# PLL1.net
KiCad netlist of a schematic drawn in Altium Designer
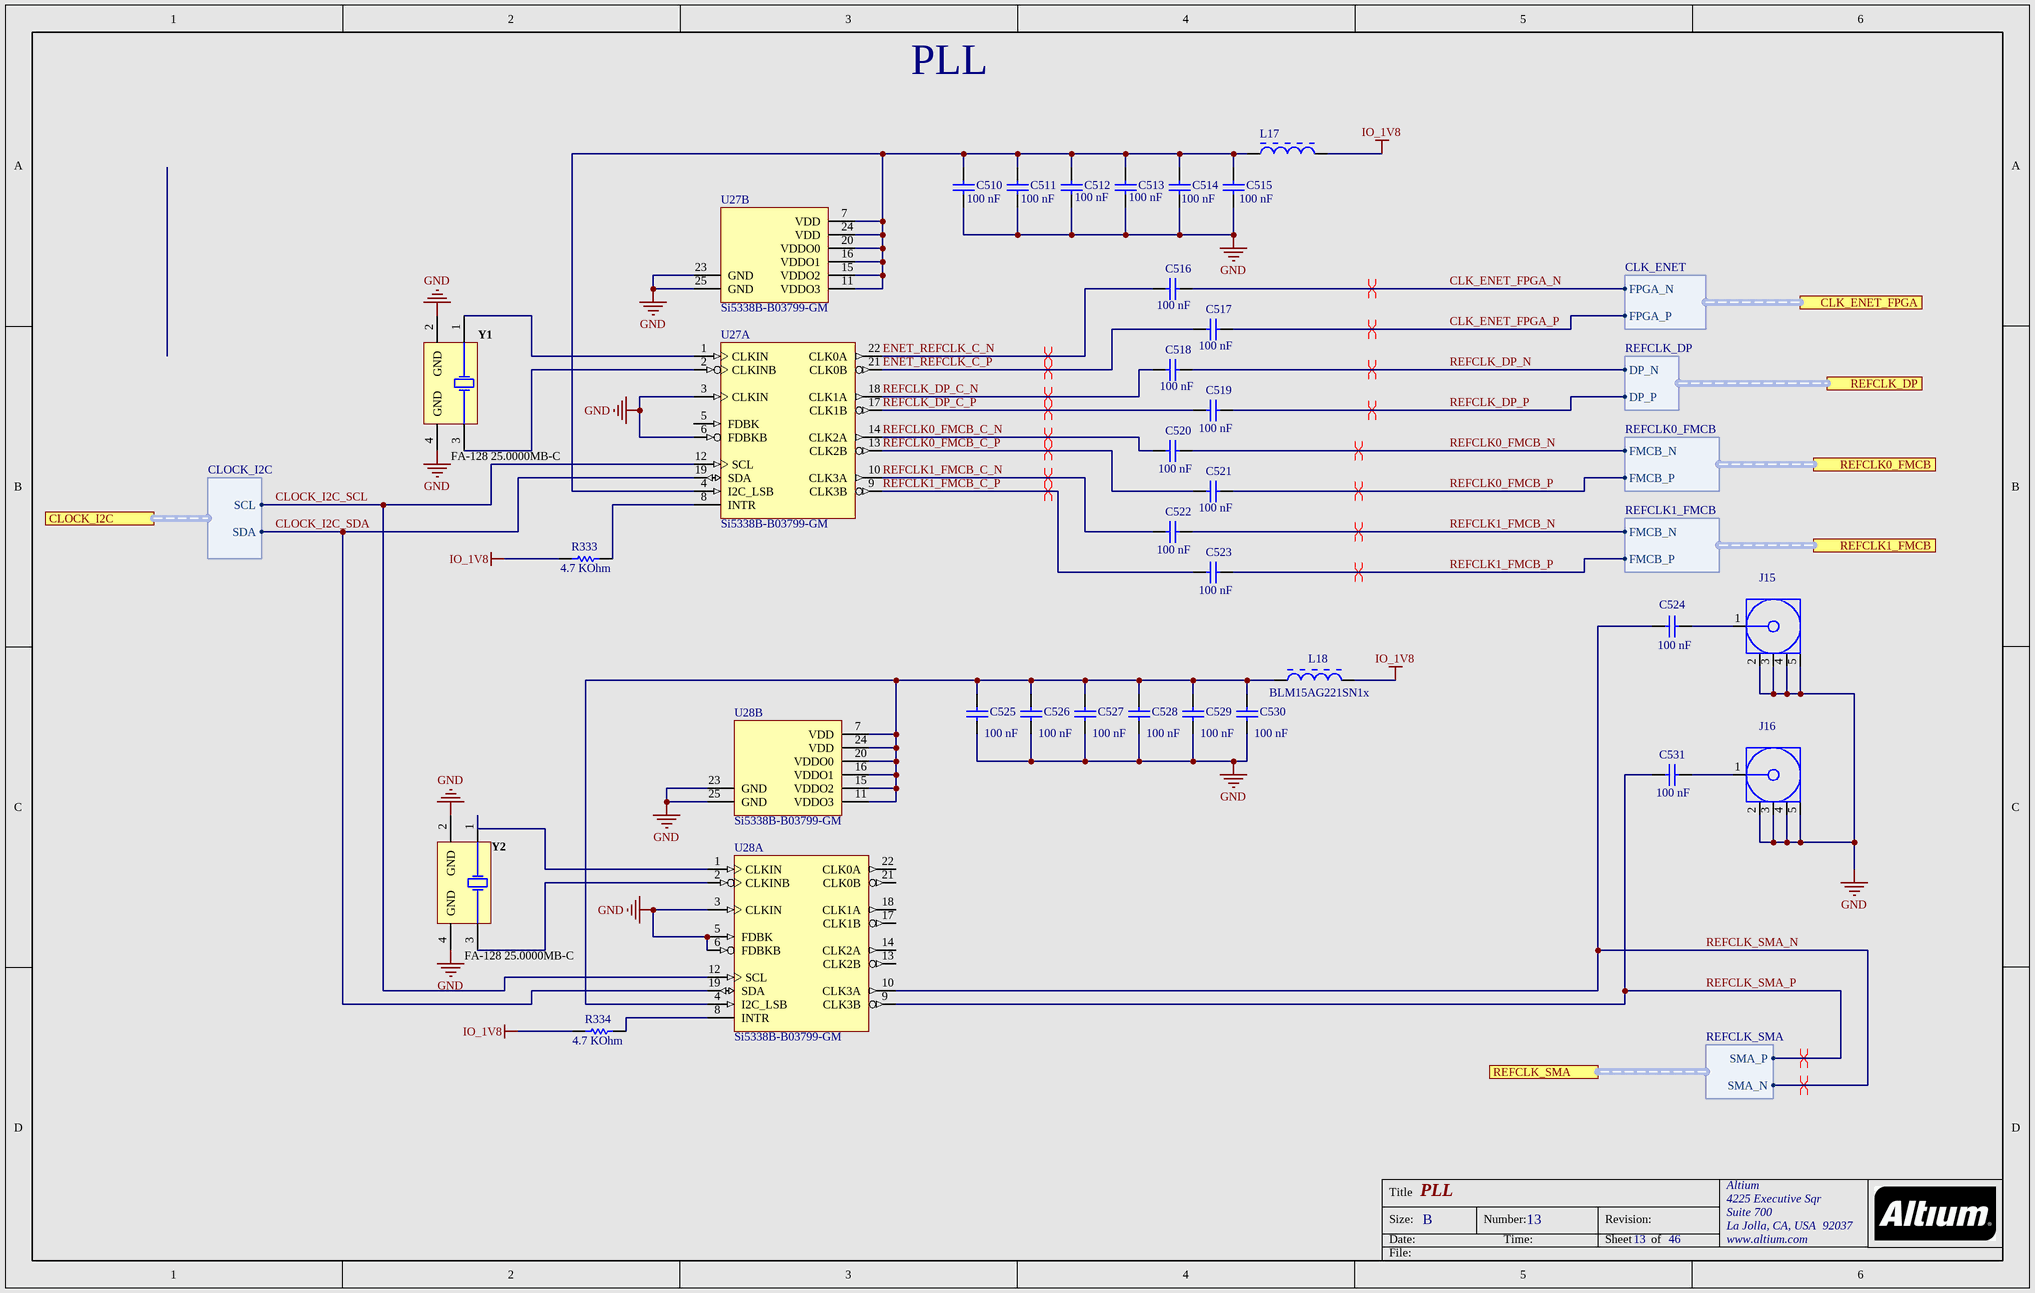
[diagram p0: PLL1.SchDoc]

(export (version "E")
  (design (tool "Eeschema 10.0.6"))
  (components
    (comp (ref "C510")
      (value "C1005X7R1E104M")
      (footprint "CAPC1005X55X10LL05")
      (description "Chip Capacitor, 0.1 uF, +/- 20%, 25 V, -55 to 125 degC, 0402 (1005 Metric), RoHS, Tape and Reel")
      (fields (field (name "TOLERANCE") "20%") (field (name "CAPACITANCE") "100 nF"))
      (libsource (lib "Altium Content Vault") (part "CAP-NP-2"))
    )
    (comp (ref "C511")
      (value "C1005X7R1E104M")
      (footprint "CAPC1005X55X10LL05")
      (description "Chip Capacitor, 0.1 uF, +/- 20%, 25 V, -55 to 125 degC, 0402 (1005 Metric), RoHS, Tape and Reel")
      (fields (field (name "TOLERANCE") "20%") (field (name "CAPACITANCE") "100 nF"))
      (libsource (lib "Altium Content Vault") (part "CAP-NP-2"))
    )
    (comp (ref "C512")
      (value "C1005X7R1E104M")
      (footprint "CAPC1005X55X10LL05")
      (description "Chip Capacitor, 0.1 uF, +/- 20%, 25 V, -55 to 125 degC, 0402 (1005 Metric), RoHS, Tape and Reel")
      (fields (field (name "TOLERANCE") "20%") (field (name "CAPACITANCE") "100 nF"))
      (libsource (lib "Altium Content Vault") (part "CAP-NP-2"))
    )
    (comp (ref "C513")
      (value "C1005X7R1E104M")
      (footprint "CAPC1005X55X10LL05")
      (description "Chip Capacitor, 0.1 uF, +/- 20%, 25 V, -55 to 125 degC, 0402 (1005 Metric), RoHS, Tape and Reel")
      (fields (field (name "TOLERANCE") "20%") (field (name "CAPACITANCE") "100 nF"))
      (libsource (lib "Altium Content Vault") (part "CAP-NP-2"))
    )
    (comp (ref "C514")
      (value "C1005X7R1E104M")
      (footprint "CAPC1005X55X10LL05")
      (description "Chip Capacitor, 0.1 uF, +/- 20%, 25 V, -55 to 125 degC, 0402 (1005 Metric), RoHS, Tape and Reel")
      (fields (field (name "TOLERANCE") "20%") (field (name "CAPACITANCE") "100 nF"))
      (libsource (lib "Altium Content Vault") (part "CAP-NP-2"))
    )
    (comp (ref "C515")
      (value "C1005X7R1E104M")
      (footprint "CAPC1005X55X10LL05")
      (description "Chip Capacitor, 0.1 uF, +/- 20%, 25 V, -55 to 125 degC, 0402 (1005 Metric), RoHS, Tape and Reel")
      (fields (field (name "TOLERANCE") "20%") (field (name "CAPACITANCE") "100 nF"))
      (libsource (lib "Altium Content Vault") (part "CAP-NP-2"))
    )
    (comp (ref "C516")
      (value "C1005X7R1E104M")
      (footprint "CAPC1005X55X10LL05")
      (description "Chip Capacitor, 0.1 uF, +/- 20%, 25 V, -55 to 125 degC, 0402 (1005 Metric), RoHS, Tape and Reel")
      (fields (field (name "TOLERANCE") "20%") (field (name "CAPACITANCE") "100 nF"))
      (libsource (lib "Altium Content Vault") (part "CAP-NP-2"))
    )
    (comp (ref "C517")
      (value "C1005X7R1E104M")
      (footprint "CAPC1005X55X10LL05")
      (description "Chip Capacitor, 0.1 uF, +/- 20%, 25 V, -55 to 125 degC, 0402 (1005 Metric), RoHS, Tape and Reel")
      (fields (field (name "TOLERANCE") "20%") (field (name "CAPACITANCE") "100 nF"))
      (libsource (lib "Altium Content Vault") (part "CAP-NP-2"))
    )
    (comp (ref "C518")
      (value "C1005X7R1E104M")
      (footprint "CAPC1005X55X10LL05")
      (description "Chip Capacitor, 0.1 uF, +/- 20%, 25 V, -55 to 125 degC, 0402 (1005 Metric), RoHS, Tape and Reel")
      (fields (field (name "TOLERANCE") "20%") (field (name "CAPACITANCE") "100 nF"))
      (libsource (lib "Altium Content Vault") (part "CAP-NP-2"))
    )
    (comp (ref "C519")
      (value "C1005X7R1E104M")
      (footprint "CAPC1005X55X10LL05")
      (description "Chip Capacitor, 0.1 uF, +/- 20%, 25 V, -55 to 125 degC, 0402 (1005 Metric), RoHS, Tape and Reel")
      (fields (field (name "TOLERANCE") "20%") (field (name "CAPACITANCE") "100 nF"))
      (libsource (lib "Altium Content Vault") (part "CAP-NP-2"))
    )
    (comp (ref "C520")
      (value "C1005X7R1E104M")
      (footprint "CAPC1005X55X10LL05")
      (description "Chip Capacitor, 0.1 uF, +/- 20%, 25 V, -55 to 125 degC, 0402 (1005 Metric), RoHS, Tape and Reel")
      (fields (field (name "TOLERANCE") "20%") (field (name "CAPACITANCE") "100 nF"))
      (libsource (lib "Altium Content Vault") (part "CAP-NP-2"))
    )
    (comp (ref "C521")
      (value "C1005X7R1E104M")
      (footprint "CAPC1005X55X10LL05")
      (description "Chip Capacitor, 0.1 uF, +/- 20%, 25 V, -55 to 125 degC, 0402 (1005 Metric), RoHS, Tape and Reel")
      (fields (field (name "TOLERANCE") "20%") (field (name "CAPACITANCE") "100 nF"))
      (libsource (lib "Altium Content Vault") (part "CAP-NP-2"))
    )
    (comp (ref "C522")
      (value "C1005X7R1E104M")
      (footprint "CAPC1005X55X10LL05")
      (description "Chip Capacitor, 0.1 uF, +/- 20%, 25 V, -55 to 125 degC, 0402 (1005 Metric), RoHS, Tape and Reel")
      (fields (field (name "TOLERANCE") "20%") (field (name "CAPACITANCE") "100 nF"))
      (libsource (lib "Altium Content Vault") (part "CAP-NP-2"))
    )
    (comp (ref "C523")
      (value "C1005X7R1E104M")
      (footprint "CAPC1005X55X10LL05")
      (description "Chip Capacitor, 0.1 uF, +/- 20%, 25 V, -55 to 125 degC, 0402 (1005 Metric), RoHS, Tape and Reel")
      (fields (field (name "TOLERANCE") "20%") (field (name "CAPACITANCE") "100 nF"))
      (libsource (lib "Altium Content Vault") (part "CAP-NP-2"))
    )
    (comp (ref "C524")
      (value "C1005X7R1E104M")
      (footprint "CAPC1005X55X10LL05")
      (description "Chip Capacitor, 0.1 uF, +/- 20%, 25 V, -55 to 125 degC, 0402 (1005 Metric), RoHS, Tape and Reel")
      (fields (field (name "TOLERANCE") "20%") (field (name "CAPACITANCE") "100 nF"))
      (libsource (lib "Altium Content Vault") (part "CAP-NP-2"))
    )
    (comp (ref "C525")
      (value "C1005X7R1E104M")
      (footprint "CAPC1005X55X10LL05")
      (description "Chip Capacitor, 0.1 uF, +/- 20%, 25 V, -55 to 125 degC, 0402 (1005 Metric), RoHS, Tape and Reel")
      (fields (field (name "TOLERANCE") "20%") (field (name "CAPACITANCE") "100 nF"))
      (libsource (lib "Altium Content Vault") (part "CAP-NP-2"))
    )
    (comp (ref "C526")
      (value "C1005X7R1E104M")
      (footprint "CAPC1005X55X10LL05")
      (description "Chip Capacitor, 0.1 uF, +/- 20%, 25 V, -55 to 125 degC, 0402 (1005 Metric), RoHS, Tape and Reel")
      (fields (field (name "TOLERANCE") "20%") (field (name "CAPACITANCE") "100 nF"))
      (libsource (lib "Altium Content Vault") (part "CAP-NP-2"))
    )
    (comp (ref "C527")
      (value "C1005X7R1E104M")
      (footprint "CAPC1005X55X10LL05")
      (description "Chip Capacitor, 0.1 uF, +/- 20%, 25 V, -55 to 125 degC, 0402 (1005 Metric), RoHS, Tape and Reel")
      (fields (field (name "TOLERANCE") "20%") (field (name "CAPACITANCE") "100 nF"))
      (libsource (lib "Altium Content Vault") (part "CAP-NP-2"))
    )
    (comp (ref "C528")
      (value "C1005X7R1E104M")
      (footprint "CAPC1005X55X10LL05")
      (description "Chip Capacitor, 0.1 uF, +/- 20%, 25 V, -55 to 125 degC, 0402 (1005 Metric), RoHS, Tape and Reel")
      (fields (field (name "TOLERANCE") "20%") (field (name "CAPACITANCE") "100 nF"))
      (libsource (lib "Altium Content Vault") (part "CAP-NP-2"))
    )
    (comp (ref "C529")
      (value "C1005X7R1E104M")
      (footprint "CAPC1005X55X10LL05")
      (description "Chip Capacitor, 0.1 uF, +/- 20%, 25 V, -55 to 125 degC, 0402 (1005 Metric), RoHS, Tape and Reel")
      (fields (field (name "TOLERANCE") "20%") (field (name "CAPACITANCE") "100 nF"))
      (libsource (lib "Altium Content Vault") (part "CAP-NP-2"))
    )
    (comp (ref "C530")
      (value "C1005X7R1E104M")
      (footprint "CAPC1005X55X10LL05")
      (description "Chip Capacitor, 0.1 uF, +/- 20%, 25 V, -55 to 125 degC, 0402 (1005 Metric), RoHS, Tape and Reel")
      (fields (field (name "TOLERANCE") "20%") (field (name "CAPACITANCE") "100 nF"))
      (libsource (lib "Altium Content Vault") (part "CAP-NP-2"))
    )
    (comp (ref "C531")
      (value "C1005X7R1E104M")
      (footprint "CAPC1005X55X10LL05")
      (description "Chip Capacitor, 0.1 uF, +/- 20%, 25 V, -55 to 125 degC, 0402 (1005 Metric), RoHS, Tape and Reel")
      (fields (field (name "TOLERANCE") "20%") (field (name "CAPACITANCE") "100 nF"))
      (libsource (lib "Altium Content Vault") (part "CAP-NP-2"))
    )
    (comp (ref "J15")
      (value "LTI-SASF54GT")
      (footprint "LHT-LTI-SASF54GT_V")
      (description "SMA Connector, Pitch 2.54 mm, 1 Position, Height 9.5 mm, Tail Length 4 mm, RoHS")
      (fields (field (name "MANUFACTURER") "Lighthorse Technologies Inc."))
      (libsource (lib "Altium Content Vault") (part "CMP-1713-00001-1"))
    )
    (comp (ref "J16")
      (value "LTI-SASF54GT")
      (footprint "LHT-LTI-SASF54GT_V")
      (description "SMA Connector, Pitch 2.54 mm, 1 Position, Height 9.5 mm, Tail Length 4 mm, RoHS")
      (fields (field (name "MANUFACTURER") "Lighthorse Technologies Inc."))
      (libsource (lib "Altium Content Vault") (part "CMP-1713-00001-1"))
    )
    (comp (ref "L17")
      (value "BLM15AG221SN1J")
      (footprint "MURA-BLM15-CHIP-2_V")
      (fields (field (name "MANUFACTURER") "Murata"))
      (libsource (lib "Altium Content Vault") (part "CMP-0686-00186-2"))
    )
    (comp (ref "L18")
      (value "BLM15AG221SN1x")
      (footprint "MURA-BLM15AG221SN1x_V")
      (description "Chip Bead, 220 Ohm, +/- 25 %, 100 MHz, 300 mA, -55 to 125 degC, 0402 (1005 Metric), RoHS")
      (fields (field (name "TOLERANCE") "25%"))
      (libsource (lib "Altium Content Vault") (part "BEAD-2"))
    )
    (comp (ref "R333")
      (value "ERJ-2RKF4701X")
      (footprint "RESC1005X40X25LL05T05")
      (description "Chip Resistor, 4.7 KOhm, +/- 1%, 0.1 W, -55 to 155 degC, 0402 (1005 Metric), RoHS, Tape and Reel")
      (fields (field (name "TOLERANCE") "1%") (field (name "RESISTANCE") "4.7 KOhm"))
      (libsource (lib "Altium Content Vault") (part "RES-2"))
    )
    (comp (ref "R334")
      (value "ERJ-2RKF4701X")
      (footprint "RESC1005X40X25LL05T05")
      (description "Chip Resistor, 4.7 KOhm, +/- 1%, 0.1 W, -55 to 155 degC, 0402 (1005 Metric), RoHS, Tape and Reel")
      (fields (field (name "TOLERANCE") "1%") (field (name "RESISTANCE") "4.7 KOhm"))
      (libsource (lib "Altium Content Vault") (part "RES-2"))
    )
    (comp (ref "U27")
      (value "Si5338B-B03799-GM")
      (footprint "SLAB-QFN-24-2550x2550TP_V")
      (fields (field (name "MANUFACTURER") "Silicon Labs"))
      (libsource (lib "") (part "CMP-1706-00002-1_1"))
    )
    (comp (ref "U28")
      (value "Si5338B-B03799-GM")
      (footprint "SLAB-QFN-24-2550x2550TP_V")
      (fields (field (name "MANUFACTURER") "Silicon Labs"))
      (libsource (lib "Altium Content Vault") (part "CMP-1706-00002-1"))
    )
    (comp (ref "Y1")
      (value "FA-128 25.0000MB-C")
      (footprint "EPSON-FA-128_V")
      (description "Range Crystal Unit, 25 MHz, -40 to 85 degC, 4-Pin SMD, RoHS, Tape and Reel")
      (libsource (lib "Altium Content Vault") (part "XTAL-1-3-4"))
    )
    (comp (ref "Y2")
      (value "FA-128 25.0000MB-C")
      (footprint "EPSON-FA-128_V")
      (description "Range Crystal Unit, 25 MHz, -40 to 85 degC, 4-Pin SMD, RoHS, Tape and Reel")
      (libsource (lib "Altium Content Vault") (part "XTAL-1-3-4"))
    )
  )
  (nets
    (net (code "7") (name "/CLK_ENET_FPGA_N") (class "Default")
      (node (ref "C516") (pin "2") (pinfunction "2_2") (pintype "passive"))
    )
    (net (code "8") (name "/CLK_ENET_FPGA_P") (class "Default")
      (node (ref "C517") (pin "2") (pinfunction "2_2") (pintype "passive"))
    )
    (net (code "9") (name "/CLOCK_I2C_SCL") (class "Default")
      (node (ref "U27") (pin "12") (pinfunction "SCL_12") (pintype "input"))
      (node (ref "U28") (pin "12") (pinfunction "SCL_12") (pintype "input"))
    )
    (net (code "10") (name "/CLOCK_I2C_SDA") (class "Default")
      (node (ref "U27") (pin "19") (pinfunction "SDA_19") (pintype "bidirectional"))
      (node (ref "U28") (pin "19") (pinfunction "SDA_19") (pintype "bidirectional"))
    )
    (net (code "11") (name "/ENET_REFCLK_C_N") (class "Default")
      (node (ref "C516") (pin "1") (pinfunction "1_1") (pintype "passive"))
      (node (ref "U27") (pin "22") (pinfunction "CLK0A_22") (pintype "output"))
    )
    (net (code "12") (name "/ENET_REFCLK_C_P") (class "Default")
      (node (ref "C517") (pin "1") (pinfunction "1_1") (pintype "passive"))
      (node (ref "U27") (pin "21") (pinfunction "CLK0B_21") (pintype "output"))
    )
    (net (code "13") (name "/REFCLK0_FMCB_C_N") (class "Default")
      (node (ref "C520") (pin "1") (pinfunction "1_1") (pintype "passive"))
      (node (ref "U27") (pin "14") (pinfunction "CLK2A_14") (pintype "output"))
    )
    (net (code "14") (name "/REFCLK0_FMCB_C_P") (class "Default")
      (node (ref "C521") (pin "1") (pinfunction "1_1") (pintype "passive"))
      (node (ref "U27") (pin "13") (pinfunction "CLK2B_13") (pintype "output"))
    )
    (net (code "15") (name "/REFCLK0_FMCB_N") (class "Default")
      (node (ref "C520") (pin "2") (pinfunction "2_2") (pintype "passive"))
    )
    (net (code "16") (name "/REFCLK0_FMCB_P") (class "Default")
      (node (ref "C521") (pin "2") (pinfunction "2_2") (pintype "passive"))
    )
    (net (code "17") (name "/REFCLK1_FMCB_C_N") (class "Default")
      (node (ref "C522") (pin "1") (pinfunction "1_1") (pintype "passive"))
      (node (ref "U27") (pin "10") (pinfunction "CLK3A_10") (pintype "output"))
    )
    (net (code "18") (name "/REFCLK1_FMCB_C_P") (class "Default")
      (node (ref "C523") (pin "1") (pinfunction "1_1") (pintype "passive"))
      (node (ref "U27") (pin "9") (pinfunction "CLK3B_9") (pintype "output"))
    )
    (net (code "19") (name "/REFCLK1_FMCB_N") (class "Default")
      (node (ref "C522") (pin "2") (pinfunction "2_2") (pintype "passive"))
    )
    (net (code "20") (name "/REFCLK1_FMCB_P") (class "Default")
      (node (ref "C523") (pin "2") (pinfunction "2_2") (pintype "passive"))
    )
    (net (code "21") (name "/REFCLK_DP_C_N") (class "Default")
      (node (ref "C518") (pin "1") (pinfunction "1_1") (pintype "passive"))
      (node (ref "U27") (pin "18") (pinfunction "CLK1A_18") (pintype "output"))
    )
    (net (code "22") (name "/REFCLK_DP_C_P") (class "Default")
      (node (ref "C519") (pin "1") (pinfunction "1_1") (pintype "passive"))
      (node (ref "U27") (pin "17") (pinfunction "CLK1B_17") (pintype "output"))
    )
    (net (code "23") (name "/REFCLK_DP_N") (class "Default")
      (node (ref "C518") (pin "2") (pinfunction "2_2") (pintype "passive"))
    )
    (net (code "24") (name "/REFCLK_DP_P") (class "Default")
      (node (ref "C519") (pin "2") (pinfunction "2_2") (pintype "passive"))
    )
    (net (code "25") (name "/REFCLK_SMA_N") (class "Default")
      (node (ref "C524") (pin "1") (pinfunction "1_1") (pintype "passive"))
      (node (ref "U28") (pin "10") (pinfunction "CLK3A_10") (pintype "output"))
    )
    (net (code "26") (name "/REFCLK_SMA_P") (class "Default")
      (node (ref "C531") (pin "1") (pinfunction "1_1") (pintype "passive"))
      (node (ref "U28") (pin "9") (pinfunction "CLK3B_9") (pintype "output"))
    )
    (net (code "33") (name "GND") (class "Default")
      (node (ref "C510") (pin "2") (pinfunction "2_2") (pintype "passive"))
      (node (ref "C511") (pin "2") (pinfunction "2_2") (pintype "passive"))
      (node (ref "C512") (pin "2") (pinfunction "2_2") (pintype "passive"))
      (node (ref "C513") (pin "2") (pinfunction "2_2") (pintype "passive"))
      (node (ref "C514") (pin "2") (pinfunction "2_2") (pintype "passive"))
      (node (ref "C515") (pin "2") (pinfunction "2_2") (pintype "passive"))
      (node (ref "C525") (pin "2") (pinfunction "2_2") (pintype "passive"))
      (node (ref "C526") (pin "2") (pinfunction "2_2") (pintype "passive"))
      (node (ref "C527") (pin "2") (pinfunction "2_2") (pintype "passive"))
      (node (ref "C528") (pin "2") (pinfunction "2_2") (pintype "passive"))
      (node (ref "C529") (pin "2") (pinfunction "2_2") (pintype "passive"))
      (node (ref "C530") (pin "2") (pinfunction "2_2") (pintype "passive"))
      (node (ref "J15") (pin "2") (pinfunction "2_2") (pintype "passive"))
      (node (ref "J15") (pin "3") (pinfunction "3_3") (pintype "passive"))
      (node (ref "J15") (pin "4") (pinfunction "4_4") (pintype "passive"))
      (node (ref "J15") (pin "5") (pinfunction "5_5") (pintype "passive"))
      (node (ref "J16") (pin "2") (pinfunction "2_2") (pintype "passive"))
      (node (ref "J16") (pin "3") (pinfunction "3_3") (pintype "passive"))
      (node (ref "J16") (pin "4") (pinfunction "4_4") (pintype "passive"))
      (node (ref "J16") (pin "5") (pinfunction "5_5") (pintype "passive"))
      (node (ref "U27") (pin "23") (pinfunction "GND_23") (pintype "power_in"))
      (node (ref "U27") (pin "25") (pinfunction "GND_25") (pintype "power_in"))
      (node (ref "U27") (pin "3") (pinfunction "CLKIN_3") (pintype "input"))
      (node (ref "U27") (pin "6") (pinfunction "FDBKB_6") (pintype "input"))
      (node (ref "U28") (pin "23") (pinfunction "GND_23") (pintype "power_in"))
      (node (ref "U28") (pin "25") (pinfunction "GND_25") (pintype "power_in"))
      (node (ref "U28") (pin "3") (pinfunction "CLKIN_3") (pintype "input"))
      (node (ref "U28") (pin "5") (pinfunction "FDBK_5") (pintype "input"))
      (node (ref "U28") (pin "6") (pinfunction "FDBKB_6") (pintype "input"))
      (node (ref "Y1") (pin "2") (pinfunction "GND_2") (pintype "power_in"))
      (node (ref "Y1") (pin "4") (pinfunction "GND_4") (pintype "power_in"))
      (node (ref "Y2") (pin "2") (pinfunction "GND_2") (pintype "power_in"))
      (node (ref "Y2") (pin "4") (pinfunction "GND_4") (pintype "power_in"))
    )
    (net (code "34") (name "IO_1V8") (class "Default")
      (node (ref "L17") (pin "2") (pinfunction "2_2") (pintype "passive"))
      (node (ref "L18") (pin "2") (pinfunction "2_2") (pintype "passive"))
      (node (ref "R333") (pin "1") (pinfunction "1_1") (pintype "passive"))
      (node (ref "R334") (pin "1") (pinfunction "1_1") (pintype "passive"))
    )
    (net (code "35") (name "Net-(C524-Pad2)") (class "Default")
      (node (ref "C524") (pin "2") (pinfunction "2_2") (pintype "passive"))
      (node (ref "J15") (pin "1") (pinfunction "1_1") (pintype "passive"))
    )
    (net (code "36") (name "Net-(C531-Pad2)") (class "Default")
      (node (ref "C531") (pin "2") (pinfunction "2_2") (pintype "passive"))
      (node (ref "J16") (pin "1") (pinfunction "1_1") (pintype "passive"))
    )
    (net (code "37") (name "Net-(U27A-CLKINB)") (class "Default")
      (node (ref "U27") (pin "2") (pinfunction "CLKINB_2") (pintype "input"))
      (node (ref "Y1") (pin "3") (pinfunction "X2_3") (pintype "passive"))
    )
    (net (code "38") (name "Net-(U27A-I2C_LSB)") (class "Default")
      (node (ref "C510") (pin "1") (pinfunction "1_1") (pintype "passive"))
      (node (ref "C511") (pin "1") (pinfunction "1_1") (pintype "passive"))
      (node (ref "C512") (pin "1") (pinfunction "1_1") (pintype "passive"))
      (node (ref "C513") (pin "1") (pinfunction "1_1") (pintype "passive"))
      (node (ref "C514") (pin "1") (pinfunction "1_1") (pintype "passive"))
      (node (ref "C515") (pin "1") (pinfunction "1_1") (pintype "passive"))
      (node (ref "L17") (pin "1") (pinfunction "1_1") (pintype "passive"))
      (node (ref "U27") (pin "11") (pinfunction "VDDO3_11") (pintype "power_in"))
      (node (ref "U27") (pin "15") (pinfunction "VDDO2_15") (pintype "power_in"))
      (node (ref "U27") (pin "16") (pinfunction "VDDO1_16") (pintype "power_in"))
      (node (ref "U27") (pin "20") (pinfunction "VDDO0_20") (pintype "power_in"))
      (node (ref "U27") (pin "24") (pinfunction "VDD_24") (pintype "power_in"))
      (node (ref "U27") (pin "4") (pinfunction "I2C_LSB_4") (pintype "input"))
      (node (ref "U27") (pin "7") (pinfunction "VDD_7") (pintype "power_in"))
    )
    (net (code "39") (name "Net-(U27A-INTR)") (class "Default")
      (node (ref "R333") (pin "2") (pinfunction "2_2") (pintype "passive"))
      (node (ref "U27") (pin "8") (pinfunction "INTR_8") (pintype "open_collector"))
    )
    (net (code "40") (name "Net-(U28A-CLKINB)") (class "Default")
      (node (ref "U28") (pin "2") (pinfunction "CLKINB_2") (pintype "input"))
      (node (ref "Y2") (pin "3") (pinfunction "X2_3") (pintype "passive"))
    )
    (net (code "41") (name "Net-(U28A-I2C_LSB)") (class "Default")
      (node (ref "C525") (pin "1") (pinfunction "1_1") (pintype "passive"))
      (node (ref "C526") (pin "1") (pinfunction "1_1") (pintype "passive"))
      (node (ref "C527") (pin "1") (pinfunction "1_1") (pintype "passive"))
      (node (ref "C528") (pin "1") (pinfunction "1_1") (pintype "passive"))
      (node (ref "C529") (pin "1") (pinfunction "1_1") (pintype "passive"))
      (node (ref "C530") (pin "1") (pinfunction "1_1") (pintype "passive"))
      (node (ref "L18") (pin "1") (pinfunction "1_1") (pintype "passive"))
      (node (ref "U28") (pin "11") (pinfunction "VDDO3_11") (pintype "power_in"))
      (node (ref "U28") (pin "15") (pinfunction "VDDO2_15") (pintype "power_in"))
      (node (ref "U28") (pin "16") (pinfunction "VDDO1_16") (pintype "power_in"))
      (node (ref "U28") (pin "20") (pinfunction "VDDO0_20") (pintype "power_in"))
      (node (ref "U28") (pin "24") (pinfunction "VDD_24") (pintype "power_in"))
      (node (ref "U28") (pin "4") (pinfunction "I2C_LSB_4") (pintype "input"))
      (node (ref "U28") (pin "7") (pinfunction "VDD_7") (pintype "power_in"))
    )
    (net (code "42") (name "Net-(U28A-INTR)") (class "Default")
      (node (ref "R334") (pin "2") (pinfunction "2_2") (pintype "passive"))
      (node (ref "U28") (pin "8") (pinfunction "INTR_8") (pintype "open_collector"))
    )
    (net (code "43") (name "Net-(Y1-X1)") (class "Default")
      (node (ref "U27") (pin "1") (pinfunction "CLKIN_1") (pintype "input"))
      (node (ref "Y1") (pin "1") (pinfunction "X1_1") (pintype "passive"))
    )
    (net (code "44") (name "Net-(Y2-X1)") (class "Default")
      (node (ref "U28") (pin "1") (pinfunction "CLKIN_1") (pintype "input"))
      (node (ref "Y2") (pin "1") (pinfunction "X1_1") (pintype "passive"))
    )
    (net (code "45") (name "unconnected-(U27A-FDBK-Pad5)") (class "Default")
      (node (ref "U27") (pin "5") (pinfunction "FDBK_5") (pintype "input"))
    )
    (net (code "46") (name "unconnected-(U28A-CLK0A-Pad22)") (class "Default")
      (node (ref "U28") (pin "22") (pinfunction "CLK0A_22") (pintype "output"))
    )
    (net (code "47") (name "unconnected-(U28A-CLK0B-Pad21)") (class "Default")
      (node (ref "U28") (pin "21") (pinfunction "CLK0B_21") (pintype "output"))
    )
    (net (code "48") (name "unconnected-(U28A-CLK1A-Pad18)") (class "Default")
      (node (ref "U28") (pin "18") (pinfunction "CLK1A_18") (pintype "output"))
    )
    (net (code "49") (name "unconnected-(U28A-CLK1B-Pad17)") (class "Default")
      (node (ref "U28") (pin "17") (pinfunction "CLK1B_17") (pintype "output"))
    )
    (net (code "50") (name "unconnected-(U28A-CLK2A-Pad14)") (class "Default")
      (node (ref "U28") (pin "14") (pinfunction "CLK2A_14") (pintype "output"))
    )
    (net (code "51") (name "unconnected-(U28A-CLK2B-Pad13)") (class "Default")
      (node (ref "U28") (pin "13") (pinfunction "CLK2B_13") (pintype "output"))
    )
  )
)
